# zxld383-boost-driver-12mm-mk-2.net
KiCad netlist of a schematic drawn in EAGLE
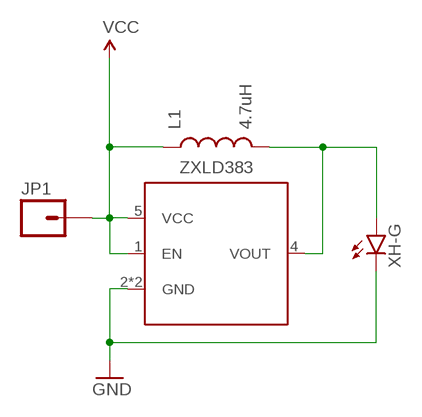
[diagram p0: schematic, sheet 1]

(export (version "E")
  (design (tool "Eeschema 10.0.6"))
  (components
    (comp (ref "JP1")
      (value "M01NOT-A-VIA-NOPE")
      (footprint "eagle-import:1X01_NOSILK_NOSTOP")
      (libsource (lib "eagle-import") (part "M01NOT-A-VIA-NOPE"))
    )
    (comp (ref "L1")
      (value "4.7uH")
      (footprint "eagle-import:1007")
      (libsource (lib "eagle-import") (part "INDUCTOR1007"))
    )
    (comp (ref "XH-G")
      (value "LEDXH-G")
      (footprint "eagle-import:CREE-XLAMP-XH-G")
      (libsource (lib "eagle-import") (part "LEDXH-G"))
    )
    (comp (ref "ZXLD383")
      (value "ZXLD383")
      (footprint "eagle-import:TSOT-23-5")
      (libsource (lib "eagle-import") (part "ZXLD383"))
    )
  )
  (nets
    (net (code "1") (name "GND") (class "Default")
      (node (ref "XH-G") (pin "K") (pinfunction "C_K") (pintype "passive"))
      (node (ref "ZXLD383") (pin "2") (pinfunction "GND_2") (pintype "bidirectional"))
      (node (ref "ZXLD383") (pin "3") (pinfunction "GND_3") (pintype "bidirectional"))
    )
    (net (code "2") (name "Net-(ZXLD383-VOUT)") (class "Default")
      (node (ref "L1") (pin "2") (pinfunction "2_2") (pintype "passive"))
      (node (ref "XH-G") (pin "A") (pinfunction "A_A") (pintype "passive"))
      (node (ref "ZXLD383") (pin "4") (pinfunction "VOUT_4") (pintype "bidirectional"))
    )
    (net (code "3") (name "VCC") (class "Default")
      (node (ref "JP1") (pin "P$1") (pinfunction "1_P$1") (pintype "passive"))
      (node (ref "L1") (pin "1") (pinfunction "1_1") (pintype "passive"))
      (node (ref "ZXLD383") (pin "1") (pinfunction "EN_1") (pintype "bidirectional"))
      (node (ref "ZXLD383") (pin "5") (pinfunction "VCC_5") (pintype "bidirectional"))
    )
  )
)
